# spokepov.net
KiCad netlist of a schematic drawn in EAGLE
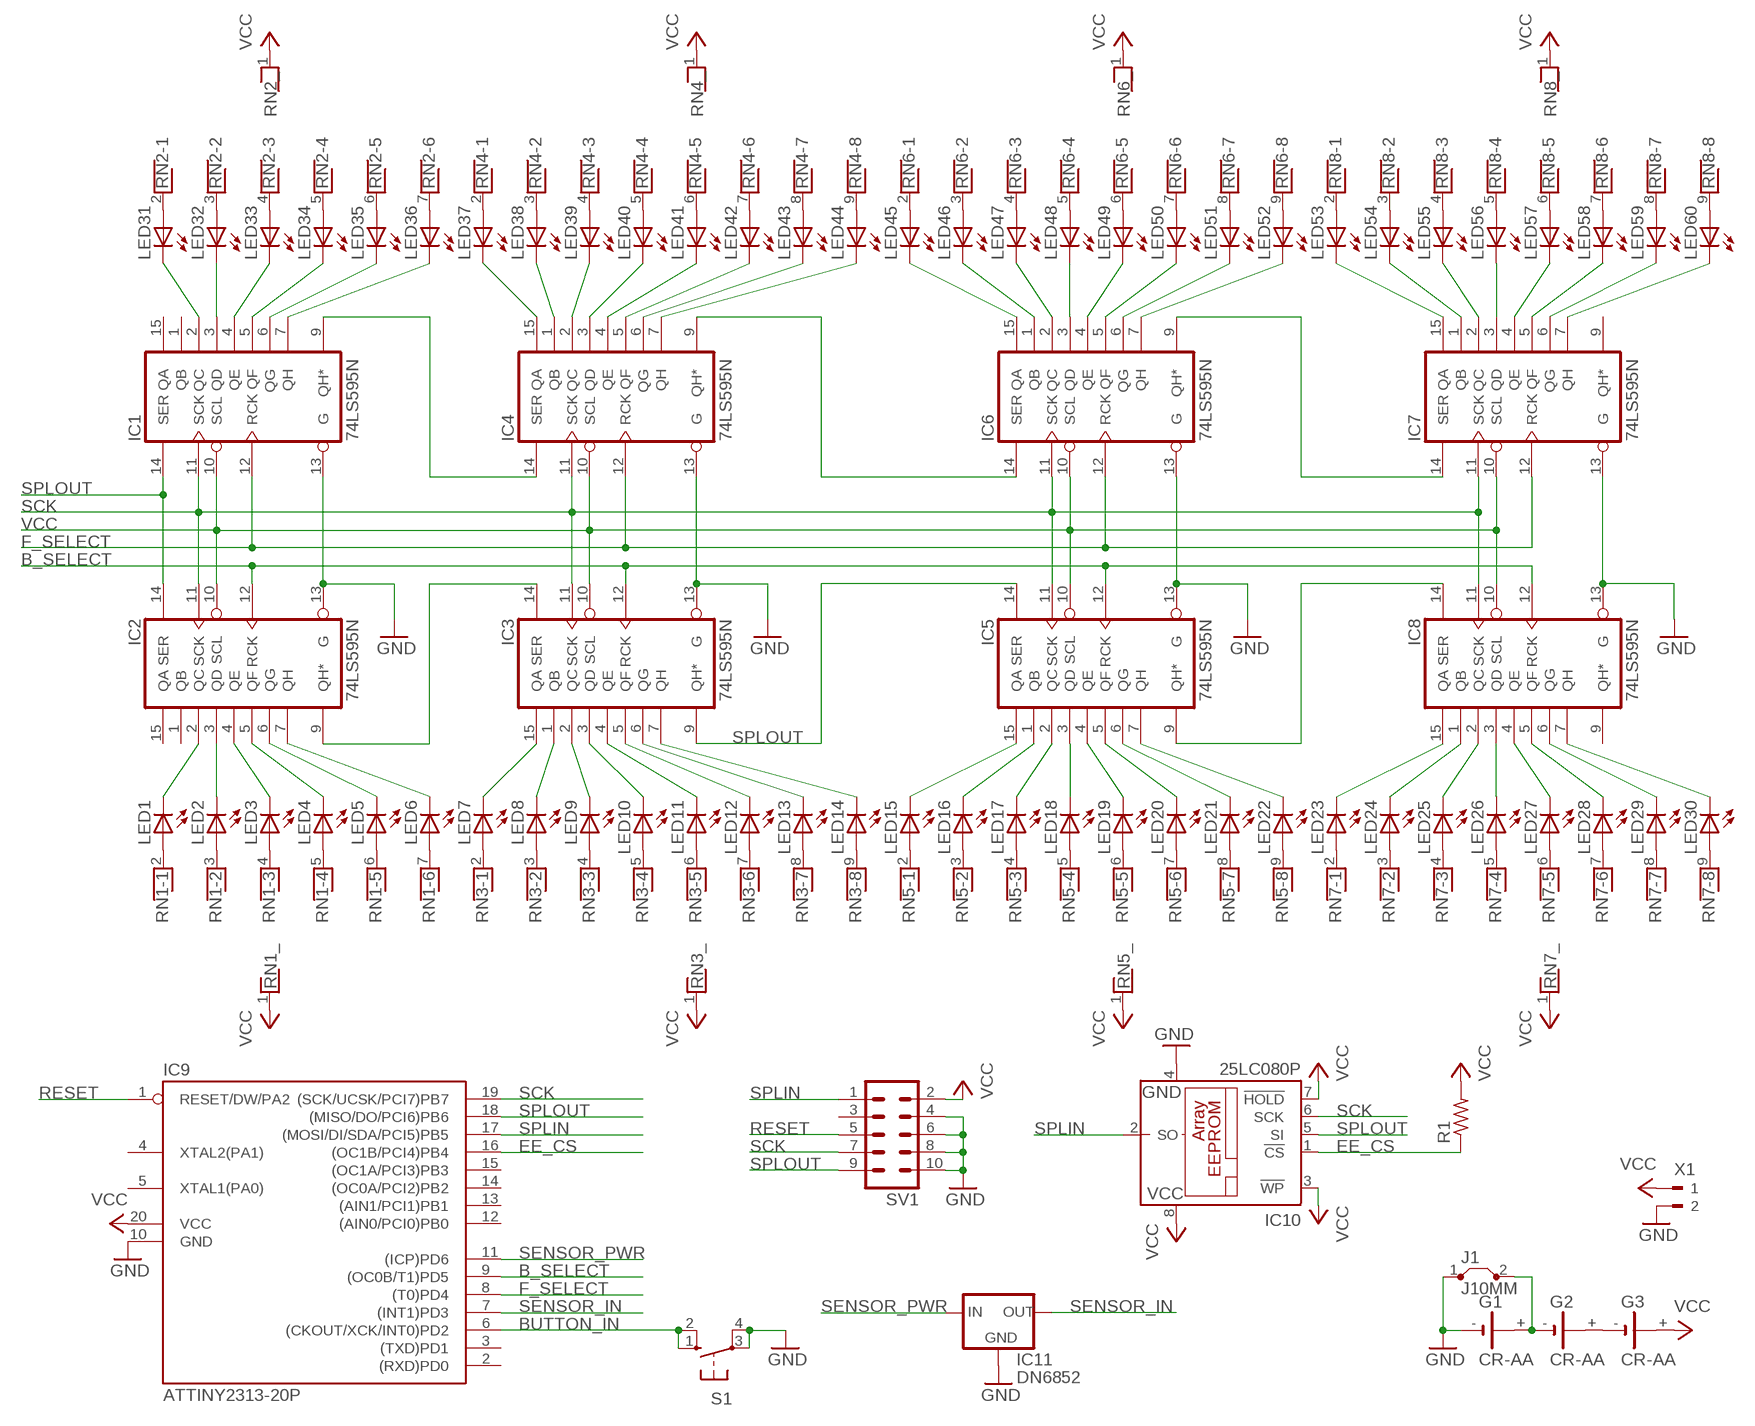
[diagram p0: schematic, sheet 1]

(export (version "E")
  (design (tool "Eeschema 10.0.6"))
  (components
    (comp (ref "G1")
      (value "CR-AA")
      (footprint "eagle-import:CRAA")
      (libsource (lib "eagle-import") (part "CR-AA"))
    )
    (comp (ref "G2")
      (value "CR-AA")
      (footprint "eagle-import:CRAA")
      (libsource (lib "eagle-import") (part "CR-AA"))
    )
    (comp (ref "G3")
      (value "CR-AA")
      (footprint "eagle-import:CRAA")
      (libsource (lib "eagle-import") (part "CR-AA"))
    )
    (comp (ref "IC1")
      (value "74LS595N")
      (footprint "eagle-import:DIL16")
      (libsource (lib "eagle-import") (part "74595NLS"))
    )
    (comp (ref "IC2")
      (value "74LS595N")
      (footprint "eagle-import:DIL16")
      (libsource (lib "eagle-import") (part "74595NLS"))
    )
    (comp (ref "IC3")
      (value "74LS595N")
      (footprint "eagle-import:DIL16")
      (libsource (lib "eagle-import") (part "74595NLS"))
    )
    (comp (ref "IC4")
      (value "74LS595N")
      (footprint "eagle-import:DIL16")
      (libsource (lib "eagle-import") (part "74595NLS"))
    )
    (comp (ref "IC5")
      (value "74LS595N")
      (footprint "eagle-import:DIL16")
      (libsource (lib "eagle-import") (part "74595NLS"))
    )
    (comp (ref "IC6")
      (value "74LS595N")
      (footprint "eagle-import:DIL16")
      (libsource (lib "eagle-import") (part "74595NLS"))
    )
    (comp (ref "IC7")
      (value "74LS595N")
      (footprint "eagle-import:DIL16")
      (libsource (lib "eagle-import") (part "74595NLS"))
    )
    (comp (ref "IC8")
      (value "74LS595N")
      (footprint "eagle-import:DIL16")
      (libsource (lib "eagle-import") (part "74595NLS"))
    )
    (comp (ref "IC9")
      (value "ATTINY2313-20P")
      (footprint "eagle-import:DIL20")
      (libsource (lib "eagle-import") (part "ATTINY2313P-20"))
    )
    (comp (ref "IC10")
      (value "25LC080P")
      (footprint "eagle-import:DIL8")
      (fields (field (name "MF") "MICROCHIP") (field (name "MPN") "25LC080/P"))
      (libsource (lib "eagle-import") (part "25PLC080"))
    )
    (comp (ref "IC11")
      (value "DN6852")
      (footprint "eagle-import:78MXXS")
      (libsource (lib "eagle-import") (part "78MXXS"))
    )
    (comp (ref "J1")
      (value "J10MM")
      (footprint "eagle-import:10")
      (libsource (lib "eagle-import") (part "J10MM"))
    )
    (comp (ref "LED1")
      (value "LED5MM")
      (footprint "eagle-import:LED5MM")
      (libsource (lib "eagle-import") (part "LED5MM"))
    )
    (comp (ref "LED2")
      (value "LED5MM")
      (footprint "eagle-import:LED5MM")
      (libsource (lib "eagle-import") (part "LED5MM"))
    )
    (comp (ref "LED3")
      (value "LED5MM")
      (footprint "eagle-import:LED5MM")
      (libsource (lib "eagle-import") (part "LED5MM"))
    )
    (comp (ref "LED4")
      (value "LED5MM")
      (footprint "eagle-import:LED5MM")
      (libsource (lib "eagle-import") (part "LED5MM"))
    )
    (comp (ref "LED5")
      (value "LED5MM")
      (footprint "eagle-import:LED5MM")
      (libsource (lib "eagle-import") (part "LED5MM"))
    )
    (comp (ref "LED6")
      (value "LED5MM")
      (footprint "eagle-import:LED5MM")
      (libsource (lib "eagle-import") (part "LED5MM"))
    )
    (comp (ref "LED7")
      (value "LED5MM")
      (footprint "eagle-import:LED5MM")
      (libsource (lib "eagle-import") (part "LED5MM"))
    )
    (comp (ref "LED8")
      (value "LED5MM")
      (footprint "eagle-import:LED5MM")
      (libsource (lib "eagle-import") (part "LED5MM"))
    )
    (comp (ref "LED9")
      (value "LED5MM")
      (footprint "eagle-import:LED5MM")
      (libsource (lib "eagle-import") (part "LED5MM"))
    )
    (comp (ref "LED10")
      (value "LED5MM")
      (footprint "eagle-import:LED5MM")
      (libsource (lib "eagle-import") (part "LED5MM"))
    )
    (comp (ref "LED11")
      (value "LED5MM")
      (footprint "eagle-import:LED5MM")
      (libsource (lib "eagle-import") (part "LED5MM"))
    )
    (comp (ref "LED12")
      (value "LED5MM")
      (footprint "eagle-import:LED5MM")
      (libsource (lib "eagle-import") (part "LED5MM"))
    )
    (comp (ref "LED13")
      (value "LED5MM")
      (footprint "eagle-import:LED5MM")
      (libsource (lib "eagle-import") (part "LED5MM"))
    )
    (comp (ref "LED14")
      (value "LED5MM")
      (footprint "eagle-import:LED5MM")
      (libsource (lib "eagle-import") (part "LED5MM"))
    )
    (comp (ref "LED15")
      (value "LED5MM")
      (footprint "eagle-import:LED5MM")
      (libsource (lib "eagle-import") (part "LED5MM"))
    )
    (comp (ref "LED16")
      (value "LED5MM")
      (footprint "eagle-import:LED5MM")
      (libsource (lib "eagle-import") (part "LED5MM"))
    )
    (comp (ref "LED17")
      (value "LED5MM")
      (footprint "eagle-import:LED5MM")
      (libsource (lib "eagle-import") (part "LED5MM"))
    )
    (comp (ref "LED18")
      (value "LED5MM")
      (footprint "eagle-import:LED5MM")
      (libsource (lib "eagle-import") (part "LED5MM"))
    )
    (comp (ref "LED19")
      (value "LED5MM")
      (footprint "eagle-import:LED5MM")
      (libsource (lib "eagle-import") (part "LED5MM"))
    )
    (comp (ref "LED20")
      (value "LED5MM")
      (footprint "eagle-import:LED5MM")
      (libsource (lib "eagle-import") (part "LED5MM"))
    )
    (comp (ref "LED21")
      (value "LED5MM")
      (footprint "eagle-import:LED5MM")
      (libsource (lib "eagle-import") (part "LED5MM"))
    )
    (comp (ref "LED22")
      (value "LED5MM")
      (footprint "eagle-import:LED5MM")
      (libsource (lib "eagle-import") (part "LED5MM"))
    )
    (comp (ref "LED23")
      (value "LED5MM")
      (footprint "eagle-import:LED5MM")
      (libsource (lib "eagle-import") (part "LED5MM"))
    )
    (comp (ref "LED24")
      (value "LED5MM")
      (footprint "eagle-import:LED5MM")
      (libsource (lib "eagle-import") (part "LED5MM"))
    )
    (comp (ref "LED25")
      (value "LED5MM")
      (footprint "eagle-import:LED5MM")
      (libsource (lib "eagle-import") (part "LED5MM"))
    )
    (comp (ref "LED26")
      (value "LED5MM")
      (footprint "eagle-import:LED5MM")
      (libsource (lib "eagle-import") (part "LED5MM"))
    )
    (comp (ref "LED27")
      (value "LED5MM")
      (footprint "eagle-import:LED5MM")
      (libsource (lib "eagle-import") (part "LED5MM"))
    )
    (comp (ref "LED28")
      (value "LED5MM")
      (footprint "eagle-import:LED5MM")
      (libsource (lib "eagle-import") (part "LED5MM"))
    )
    (comp (ref "LED29")
      (value "LED5MM")
      (footprint "eagle-import:LED5MM")
      (libsource (lib "eagle-import") (part "LED5MM"))
    )
    (comp (ref "LED30")
      (value "LED5MM")
      (footprint "eagle-import:LED5MM")
      (libsource (lib "eagle-import") (part "LED5MM"))
    )
    (comp (ref "LED31")
      (value "LED5MM")
      (footprint "eagle-import:LED5MM")
      (libsource (lib "eagle-import") (part "LED5MM"))
    )
    (comp (ref "LED32")
      (value "LED5MM")
      (footprint "eagle-import:LED5MM")
      (libsource (lib "eagle-import") (part "LED5MM"))
    )
    (comp (ref "LED33")
      (value "LED5MM")
      (footprint "eagle-import:LED5MM")
      (libsource (lib "eagle-import") (part "LED5MM"))
    )
    (comp (ref "LED34")
      (value "LED5MM")
      (footprint "eagle-import:LED5MM")
      (libsource (lib "eagle-import") (part "LED5MM"))
    )
    (comp (ref "LED35")
      (value "LED5MM")
      (footprint "eagle-import:LED5MM")
      (libsource (lib "eagle-import") (part "LED5MM"))
    )
    (comp (ref "LED36")
      (value "LED5MM")
      (footprint "eagle-import:LED5MM")
      (libsource (lib "eagle-import") (part "LED5MM"))
    )
    (comp (ref "LED37")
      (value "LED5MM")
      (footprint "eagle-import:LED5MM")
      (libsource (lib "eagle-import") (part "LED5MM"))
    )
    (comp (ref "LED38")
      (value "LED5MM")
      (footprint "eagle-import:LED5MM")
      (libsource (lib "eagle-import") (part "LED5MM"))
    )
    (comp (ref "LED39")
      (value "LED5MM")
      (footprint "eagle-import:LED5MM")
      (libsource (lib "eagle-import") (part "LED5MM"))
    )
    (comp (ref "LED40")
      (value "LED5MM")
      (footprint "eagle-import:LED5MM")
      (libsource (lib "eagle-import") (part "LED5MM"))
    )
    (comp (ref "LED41")
      (value "LED5MM")
      (footprint "eagle-import:LED5MM")
      (libsource (lib "eagle-import") (part "LED5MM"))
    )
    (comp (ref "LED42")
      (value "LED5MM")
      (footprint "eagle-import:LED5MM")
      (libsource (lib "eagle-import") (part "LED5MM"))
    )
    (comp (ref "LED43")
      (value "LED5MM")
      (footprint "eagle-import:LED5MM")
      (libsource (lib "eagle-import") (part "LED5MM"))
    )
    (comp (ref "LED44")
      (value "LED5MM")
      (footprint "eagle-import:LED5MM")
      (libsource (lib "eagle-import") (part "LED5MM"))
    )
    (comp (ref "LED45")
      (value "LED5MM")
      (footprint "eagle-import:LED5MM")
      (libsource (lib "eagle-import") (part "LED5MM"))
    )
    (comp (ref "LED46")
      (value "LED5MM")
      (footprint "eagle-import:LED5MM")
      (libsource (lib "eagle-import") (part "LED5MM"))
    )
    (comp (ref "LED47")
      (value "LED5MM")
      (footprint "eagle-import:LED5MM")
      (libsource (lib "eagle-import") (part "LED5MM"))
    )
    (comp (ref "LED48")
      (value "LED5MM")
      (footprint "eagle-import:LED5MM")
      (libsource (lib "eagle-import") (part "LED5MM"))
    )
    (comp (ref "LED49")
      (value "LED5MM")
      (footprint "eagle-import:LED5MM")
      (libsource (lib "eagle-import") (part "LED5MM"))
    )
    (comp (ref "LED50")
      (value "LED5MM")
      (footprint "eagle-import:LED5MM")
      (libsource (lib "eagle-import") (part "LED5MM"))
    )
    (comp (ref "LED51")
      (value "LED5MM")
      (footprint "eagle-import:LED5MM")
      (libsource (lib "eagle-import") (part "LED5MM"))
    )
    (comp (ref "LED52")
      (value "LED5MM")
      (footprint "eagle-import:LED5MM")
      (libsource (lib "eagle-import") (part "LED5MM"))
    )
    (comp (ref "LED53")
      (value "LED5MM")
      (footprint "eagle-import:LED5MM")
      (libsource (lib "eagle-import") (part "LED5MM"))
    )
    (comp (ref "LED54")
      (value "LED5MM")
      (footprint "eagle-import:LED5MM")
      (libsource (lib "eagle-import") (part "LED5MM"))
    )
    (comp (ref "LED55")
      (value "LED5MM")
      (footprint "eagle-import:LED5MM")
      (libsource (lib "eagle-import") (part "LED5MM"))
    )
    (comp (ref "LED56")
      (value "LED5MM")
      (footprint "eagle-import:LED5MM")
      (libsource (lib "eagle-import") (part "LED5MM"))
    )
    (comp (ref "LED57")
      (value "LED5MM")
      (footprint "eagle-import:LED5MM")
      (libsource (lib "eagle-import") (part "LED5MM"))
    )
    (comp (ref "LED58")
      (value "LED5MM")
      (footprint "eagle-import:LED5MM")
      (libsource (lib "eagle-import") (part "LED5MM"))
    )
    (comp (ref "LED59")
      (value "LED5MM")
      (footprint "eagle-import:LED5MM")
      (libsource (lib "eagle-import") (part "LED5MM"))
    )
    (comp (ref "LED60")
      (value "LED5MM")
      (footprint "eagle-import:LED5MM")
      (libsource (lib "eagle-import") (part "LED5MM"))
    )
    (comp (ref "R1")
      (value "R-US_0207/10")
      (footprint "eagle-import:0207_10")
      (libsource (lib "eagle-import") (part "R-US_0207/10"))
    )
    (comp (ref "RN1")
      (value "RNX8")
      (footprint "eagle-import:RN-9")
      (libsource (lib "eagle-import") (part "RNX8"))
    )
    (comp (ref "RN2")
      (value "RNX8")
      (footprint "eagle-import:RN-9")
      (libsource (lib "eagle-import") (part "RNX8"))
    )
    (comp (ref "RN3")
      (value "RNX8")
      (footprint "eagle-import:RN-9")
      (libsource (lib "eagle-import") (part "RNX8"))
    )
    (comp (ref "RN4")
      (value "RNX8")
      (footprint "eagle-import:RN-9")
      (libsource (lib "eagle-import") (part "RNX8"))
    )
    (comp (ref "RN5")
      (value "RNX8")
      (footprint "eagle-import:RN-9")
      (libsource (lib "eagle-import") (part "RNX8"))
    )
    (comp (ref "RN6")
      (value "RNX8")
      (footprint "eagle-import:RN-9")
      (libsource (lib "eagle-import") (part "RNX8"))
    )
    (comp (ref "RN7")
      (value "RNX8")
      (footprint "eagle-import:RN-9")
      (libsource (lib "eagle-import") (part "RNX8"))
    )
    (comp (ref "RN8")
      (value "RNX8")
      (footprint "eagle-import:RN-9")
      (libsource (lib "eagle-import") (part "RNX8"))
    )
    (comp (ref "S1")
      (value "10-XX")
      (footprint "eagle-import:B3F-10XX")
      (fields (field (name "MPN") "B3F-1000"))
      (libsource (lib "eagle-import") (part "10-XX"))
    )
    (comp (ref "SV1")
      (value "ML10")
      (footprint "eagle-import:ML10")
      (libsource (lib "eagle-import") (part "ML10"))
    )
    (comp (ref "X1")
      (value "90-2")
      (footprint "eagle-import:90-2")
      (libsource (lib "eagle-import") (part "90-2"))
    )
  )
  (nets
    (net (code "1") (name "/BUTTON_IN") (class "Default")
      (node (ref "IC9") (pin "6") (pinfunction "(CKOUT/XCK/INT0)PD2_6") (pintype "bidirectional"))
      (node (ref "S1") (pin "1") (pinfunction "S_1") (pintype "passive"))
      (node (ref "S1") (pin "2") (pinfunction "S1_2") (pintype "passive"))
    )
    (net (code "2") (name "/B_SELECT") (class "Default")
      (node (ref "IC2") (pin "12") (pinfunction "RCK_12") (pintype "input"))
      (node (ref "IC3") (pin "12") (pinfunction "RCK_12") (pintype "input"))
      (node (ref "IC5") (pin "12") (pinfunction "RCK_12") (pintype "input"))
      (node (ref "IC8") (pin "12") (pinfunction "RCK_12") (pintype "input"))
      (node (ref "IC9") (pin "9") (pinfunction "(OC0B/T1)PD5_9") (pintype "bidirectional"))
    )
    (net (code "3") (name "/EE_CS") (class "Default")
      (node (ref "IC10") (pin "1") (pinfunction "~{CS}_1") (pintype "input"))
      (node (ref "IC9") (pin "16") (pinfunction "(OC1B/PCI4)PB4_16") (pintype "bidirectional"))
      (node (ref "R1") (pin "1") (pinfunction "1_1") (pintype "passive"))
    )
    (net (code "4") (name "/F_SELECT") (class "Default")
      (node (ref "IC1") (pin "12") (pinfunction "RCK_12") (pintype "input"))
      (node (ref "IC4") (pin "12") (pinfunction "RCK_12") (pintype "input"))
      (node (ref "IC6") (pin "12") (pinfunction "RCK_12") (pintype "input"))
      (node (ref "IC7") (pin "12") (pinfunction "RCK_12") (pintype "input"))
      (node (ref "IC9") (pin "8") (pinfunction "(T0)PD4_8") (pintype "bidirectional"))
    )
    (net (code "5") (name "/RESET") (class "Default")
      (node (ref "IC9") (pin "1") (pinfunction "RESET/DW/PA2_1") (pintype "bidirectional"))
      (node (ref "SV1") (pin "5") (pinfunction "5_5") (pintype "passive"))
    )
    (net (code "6") (name "/SCK") (class "Default")
      (node (ref "IC1") (pin "11") (pinfunction "SCK_11") (pintype "input"))
      (node (ref "IC10") (pin "6") (pinfunction "SCK_6") (pintype "input"))
      (node (ref "IC2") (pin "11") (pinfunction "SCK_11") (pintype "input"))
      (node (ref "IC3") (pin "11") (pinfunction "SCK_11") (pintype "input"))
      (node (ref "IC4") (pin "11") (pinfunction "SCK_11") (pintype "input"))
      (node (ref "IC5") (pin "11") (pinfunction "SCK_11") (pintype "input"))
      (node (ref "IC6") (pin "11") (pinfunction "SCK_11") (pintype "input"))
      (node (ref "IC7") (pin "11") (pinfunction "SCK_11") (pintype "input"))
      (node (ref "IC8") (pin "11") (pinfunction "SCK_11") (pintype "input"))
      (node (ref "IC9") (pin "19") (pinfunction "(SCK/UCSK/PCI7)PB7_19") (pintype "bidirectional"))
      (node (ref "SV1") (pin "7") (pinfunction "7_7") (pintype "passive"))
    )
    (net (code "7") (name "/SENSOR_IN") (class "Default")
      (node (ref "IC11") (pin "OUT") (pinfunction "OUT_OUT") (pintype "passive"))
      (node (ref "IC9") (pin "7") (pinfunction "(INT1)PD3_7") (pintype "bidirectional"))
    )
    (net (code "8") (name "/SENSOR_PWR") (class "Default")
      (node (ref "IC11") (pin "IN") (pinfunction "IN_IN") (pintype "input"))
      (node (ref "IC9") (pin "11") (pinfunction "(ICP)PD6_11") (pintype "bidirectional"))
    )
    (net (code "9") (name "/SPLIN") (class "Default")
      (node (ref "IC10") (pin "2") (pinfunction "SO_2") (pintype "bidirectional"))
      (node (ref "IC9") (pin "17") (pinfunction "(MOSI/DI/SDA/PCI5)PB5_17") (pintype "bidirectional"))
      (node (ref "SV1") (pin "1") (pinfunction "1_1") (pintype "passive"))
    )
    (net (code "10") (name "/SPLOUT") (class "Default")
      (node (ref "IC1") (pin "14") (pinfunction "SER_14") (pintype "input"))
      (node (ref "IC10") (pin "5") (pinfunction "SI_5") (pintype "input"))
      (node (ref "IC2") (pin "14") (pinfunction "SER_14") (pintype "input"))
      (node (ref "IC3") (pin "9") (pinfunction "QH*_9") (pintype "tri_state"))
      (node (ref "IC5") (pin "14") (pinfunction "SER_14") (pintype "input"))
      (node (ref "IC9") (pin "18") (pinfunction "(MISO/DO/PCI6)PB6_18") (pintype "bidirectional"))
      (node (ref "SV1") (pin "9") (pinfunction "9_9") (pintype "passive"))
    )
    (net (code "11") (name "GND") (class "Default")
      (node (ref "G1") (pin "-") (pinfunction "-_-") (pintype "passive"))
      (node (ref "IC1") (pin "13") (pinfunction "G_13") (pintype "input"))
      (node (ref "IC10") (pin "4") (pinfunction "GND_4") (pintype "power_in"))
      (node (ref "IC11") (pin "GND") (pinfunction "GND_GND") (pintype "input"))
      (node (ref "IC2") (pin "13") (pinfunction "G_13") (pintype "input"))
      (node (ref "IC3") (pin "13") (pinfunction "G_13") (pintype "input"))
      (node (ref "IC4") (pin "13") (pinfunction "G_13") (pintype "input"))
      (node (ref "IC5") (pin "13") (pinfunction "G_13") (pintype "input"))
      (node (ref "IC6") (pin "13") (pinfunction "G_13") (pintype "input"))
      (node (ref "IC7") (pin "13") (pinfunction "G_13") (pintype "input"))
      (node (ref "IC8") (pin "13") (pinfunction "G_13") (pintype "input"))
      (node (ref "IC9") (pin "10") (pinfunction "GND_10") (pintype "power_in"))
      (node (ref "J1") (pin "1") (pinfunction "1_1") (pintype "passive"))
      (node (ref "S1") (pin "3") (pinfunction "P_3") (pintype "passive"))
      (node (ref "S1") (pin "4") (pinfunction "P1_4") (pintype "passive"))
      (node (ref "SV1") (pin "10") (pinfunction "10_10") (pintype "passive"))
      (node (ref "SV1") (pin "4") (pinfunction "4_4") (pintype "passive"))
      (node (ref "SV1") (pin "6") (pinfunction "6_6") (pintype "passive"))
      (node (ref "SV1") (pin "8") (pinfunction "8_8") (pintype "passive"))
      (node (ref "X1") (pin "2") (pinfunction "2_2") (pintype "passive"))
    )
    (net (code "12") (name "Net-(G1-Pad+)") (class "Default")
      (node (ref "G1") (pin "+") (pinfunction "+_+") (pintype "passive"))
      (node (ref "G2") (pin "-") (pinfunction "-_-") (pintype "passive"))
      (node (ref "J1") (pin "2") (pinfunction "2_2") (pintype "passive"))
    )
    (net (code "13") (name "Net-(G2-Pad+)") (class "Default")
      (node (ref "G2") (pin "+") (pinfunction "+_+") (pintype "passive"))
      (node (ref "G3") (pin "-") (pinfunction "-_-") (pintype "passive"))
    )
    (net (code "14") (name "Net-(IC1A-QC)") (class "Default")
      (node (ref "IC1") (pin "2") (pinfunction "QC_2") (pintype "tri_state"))
      (node (ref "LED31") (pin "K") (pinfunction "C_K") (pintype "passive"))
    )
    (net (code "15") (name "Net-(IC1A-QD)") (class "Default")
      (node (ref "IC1") (pin "3") (pinfunction "QD_3") (pintype "tri_state"))
      (node (ref "LED32") (pin "K") (pinfunction "C_K") (pintype "passive"))
    )
    (net (code "16") (name "Net-(IC1A-QE)") (class "Default")
      (node (ref "IC1") (pin "4") (pinfunction "QE_4") (pintype "tri_state"))
      (node (ref "LED33") (pin "K") (pinfunction "C_K") (pintype "passive"))
    )
    (net (code "17") (name "Net-(IC1A-QF)") (class "Default")
      (node (ref "IC1") (pin "5") (pinfunction "QF_5") (pintype "tri_state"))
      (node (ref "LED34") (pin "K") (pinfunction "C_K") (pintype "passive"))
    )
    (net (code "18") (name "Net-(IC1A-QG)") (class "Default")
      (node (ref "IC1") (pin "6") (pinfunction "QG_6") (pintype "tri_state"))
      (node (ref "LED35") (pin "K") (pinfunction "C_K") (pintype "passive"))
    )
    (net (code "19") (name "Net-(IC1A-QH)") (class "Default")
      (node (ref "IC1") (pin "7") (pinfunction "QH_7") (pintype "tri_state"))
      (node (ref "LED36") (pin "K") (pinfunction "C_K") (pintype "passive"))
    )
    (net (code "20") (name "Net-(IC1A-QH*)") (class "Default")
      (node (ref "IC1") (pin "9") (pinfunction "QH*_9") (pintype "tri_state"))
      (node (ref "IC4") (pin "14") (pinfunction "SER_14") (pintype "input"))
    )
    (net (code "21") (name "Net-(IC2A-QC)") (class "Default")
      (node (ref "IC2") (pin "2") (pinfunction "QC_2") (pintype "tri_state"))
      (node (ref "LED1") (pin "K") (pinfunction "C_K") (pintype "passive"))
    )
    (net (code "22") (name "Net-(IC2A-QD)") (class "Default")
      (node (ref "IC2") (pin "3") (pinfunction "QD_3") (pintype "tri_state"))
      (node (ref "LED2") (pin "K") (pinfunction "C_K") (pintype "passive"))
    )
    (net (code "23") (name "Net-(IC2A-QE)") (class "Default")
      (node (ref "IC2") (pin "4") (pinfunction "QE_4") (pintype "tri_state"))
      (node (ref "LED3") (pin "K") (pinfunction "C_K") (pintype "passive"))
    )
    (net (code "24") (name "Net-(IC2A-QF)") (class "Default")
      (node (ref "IC2") (pin "5") (pinfunction "QF_5") (pintype "tri_state"))
      (node (ref "LED4") (pin "K") (pinfunction "C_K") (pintype "passive"))
    )
    (net (code "25") (name "Net-(IC2A-QG)") (class "Default")
      (node (ref "IC2") (pin "6") (pinfunction "QG_6") (pintype "tri_state"))
      (node (ref "LED5") (pin "K") (pinfunction "C_K") (pintype "passive"))
    )
    (net (code "26") (name "Net-(IC2A-QH)") (class "Default")
      (node (ref "IC2") (pin "7") (pinfunction "QH_7") (pintype "tri_state"))
      (node (ref "LED6") (pin "K") (pinfunction "C_K") (pintype "passive"))
    )
    (net (code "27") (name "Net-(IC2A-QH*)") (class "Default")
      (node (ref "IC2") (pin "9") (pinfunction "QH*_9") (pintype "tri_state"))
      (node (ref "IC3") (pin "14") (pinfunction "SER_14") (pintype "input"))
    )
    (net (code "28") (name "Net-(IC3A-QA)") (class "Default")
      (node (ref "IC3") (pin "15") (pinfunction "QA_15") (pintype "tri_state"))
      (node (ref "LED7") (pin "K") (pinfunction "C_K") (pintype "passive"))
    )
    (net (code "29") (name "Net-(IC3A-QB)") (class "Default")
      (node (ref "IC3") (pin "1") (pinfunction "QB_1") (pintype "tri_state"))
      (node (ref "LED8") (pin "K") (pinfunction "C_K") (pintype "passive"))
    )
    (net (code "30") (name "Net-(IC3A-QC)") (class "Default")
      (node (ref "IC3") (pin "2") (pinfunction "QC_2") (pintype "tri_state"))
      (node (ref "LED9") (pin "K") (pinfunction "C_K") (pintype "passive"))
    )
    (net (code "31") (name "Net-(IC3A-QD)") (class "Default")
      (node (ref "IC3") (pin "3") (pinfunction "QD_3") (pintype "tri_state"))
      (node (ref "LED10") (pin "K") (pinfunction "C_K") (pintype "passive"))
    )
    (net (code "32") (name "Net-(IC3A-QE)") (class "Default")
      (node (ref "IC3") (pin "4") (pinfunction "QE_4") (pintype "tri_state"))
      (node (ref "LED11") (pin "K") (pinfunction "C_K") (pintype "passive"))
    )
    (net (code "33") (name "Net-(IC3A-QF)") (class "Default")
      (node (ref "IC3") (pin "5") (pinfunction "QF_5") (pintype "tri_state"))
      (node (ref "LED12") (pin "K") (pinfunction "C_K") (pintype "passive"))
    )
    (net (code "34") (name "Net-(IC3A-QG)") (class "Default")
      (node (ref "IC3") (pin "6") (pinfunction "QG_6") (pintype "tri_state"))
      (node (ref "LED13") (pin "K") (pinfunction "C_K") (pintype "passive"))
    )
    (net (code "35") (name "Net-(IC3A-QH)") (class "Default")
      (node (ref "IC3") (pin "7") (pinfunction "QH_7") (pintype "tri_state"))
      (node (ref "LED14") (pin "K") (pinfunction "C_K") (pintype "passive"))
    )
    (net (code "36") (name "Net-(IC4A-QA)") (class "Default")
      (node (ref "IC4") (pin "15") (pinfunction "QA_15") (pintype "tri_state"))
      (node (ref "LED37") (pin "K") (pinfunction "C_K") (pintype "passive"))
    )
    (net (code "37") (name "Net-(IC4A-QB)") (class "Default")
      (node (ref "IC4") (pin "1") (pinfunction "QB_1") (pintype "tri_state"))
      (node (ref "LED38") (pin "K") (pinfunction "C_K") (pintype "passive"))
    )
    (net (code "38") (name "Net-(IC4A-QC)") (class "Default")
      (node (ref "IC4") (pin "2") (pinfunction "QC_2") (pintype "tri_state"))
      (node (ref "LED39") (pin "K") (pinfunction "C_K") (pintype "passive"))
    )
    (net (code "39") (name "Net-(IC4A-QD)") (class "Default")
      (node (ref "IC4") (pin "3") (pinfunction "QD_3") (pintype "tri_state"))
      (node (ref "LED40") (pin "K") (pinfunction "C_K") (pintype "passive"))
    )
    (net (code "40") (name "Net-(IC4A-QE)") (class "Default")
      (node (ref "IC4") (pin "4") (pinfunction "QE_4") (pintype "tri_state"))
      (node (ref "LED41") (pin "K") (pinfunction "C_K") (pintype "passive"))
    )
    (net (code "41") (name "Net-(IC4A-QF)") (class "Default")
      (node (ref "IC4") (pin "5") (pinfunction "QF_5") (pintype "tri_state"))
      (node (ref "LED42") (pin "K") (pinfunction "C_K") (pintype "passive"))
    )
    (net (code "42") (name "Net-(IC4A-QG)") (class "Default")
      (node (ref "IC4") (pin "6") (pinfunction "QG_6") (pintype "tri_state"))
      (node (ref "LED43") (pin "K") (pinfunction "C_K") (pintype "passive"))
    )
    (net (code "43") (name "Net-(IC4A-QH)") (class "Default")
      (node (ref "IC4") (pin "7") (pinfunction "QH_7") (pintype "tri_state"))
      (node (ref "LED44") (pin "K") (pinfunction "C_K") (pintype "passive"))
    )
    (net (code "44") (name "Net-(IC4A-QH*)") (class "Default")
      (node (ref "IC4") (pin "9") (pinfunction "QH*_9") (pintype "tri_state"))
      (node (ref "IC6") (pin "14") (pinfunction "SER_14") (pintype "input"))
    )
    (net (code "45") (name "Net-(IC5A-QA)") (class "Default")
      (node (ref "IC5") (pin "15") (pinfunction "QA_15") (pintype "tri_state"))
      (node (ref "LED15") (pin "K") (pinfunction "C_K") (pintype "passive"))
    )
    (net (code "46") (name "Net-(IC5A-QB)") (class "Default")
      (node (ref "IC5") (pin "1") (pinfunction "QB_1") (pintype "tri_state"))
      (node (ref "LED16") (pin "K") (pinfunction "C_K") (pintype "passive"))
    )
    (net (code "47") (name "Net-(IC5A-QC)") (class "Default")
      (node (ref "IC5") (pin "2") (pinfunction "QC_2") (pintype "tri_state"))
      (node (ref "LED17") (pin "K") (pinfunction "C_K") (pintype "passive"))
    )
    (net (code "48") (name "Net-(IC5A-QD)") (class "Default")
      (node (ref "IC5") (pin "3") (pinfunction "QD_3") (pintype "tri_state"))
      (node (ref "LED18") (pin "K") (pinfunction "C_K") (pintype "passive"))
    )
    (net (code "49") (name "Net-(IC5A-QE)") (class "Default")
      (node (ref "IC5") (pin "4") (pinfunction "QE_4") (pintype "tri_state"))
      (node (ref "LED19") (pin "K") (pinfunction "C_K") (pintype "passive"))
    )
    (net (code "50") (name "Net-(IC5A-QF)") (class "Default")
      (node (ref "IC5") (pin "5") (pinfunction "QF_5") (pintype "tri_state"))
      (node (ref "LED20") (pin "K") (pinfunction "C_K") (pintype "passive"))
    )
    (net (code "51") (name "Net-(IC5A-QG)") (class "Default")
      (node (ref "IC5") (pin "6") (pinfunction "QG_6") (pintype "tri_state"))
      (node (ref "LED21") (pin "K") (pinfunction "C_K") (pintype "passive"))
    )
    (net (code "52") (name "Net-(IC5A-QH)") (class "Default")
      (node (ref "IC5") (pin "7") (pinfunction "QH_7") (pintype "tri_state"))
      (node (ref "LED22") (pin "K") (pinfunction "C_K") (pintype "passive"))
    )
    (net (code "53") (name "Net-(IC5A-QH*)") (class "Default")
      (node (ref "IC5") (pin "9") (pinfunction "QH*_9") (pintype "tri_state"))
      (node (ref "IC8") (pin "14") (pinfunction "SER_14") (pintype "input"))
    )
    (net (code "54") (name "Net-(IC6A-QA)") (class "Default")
      (node (ref "IC6") (pin "15") (pinfunction "QA_15") (pintype "tri_state"))
      (node (ref "LED45") (pin "K") (pinfunction "C_K") (pintype "passive"))
    )
    (net (code "55") (name "Net-(IC6A-QB)") (class "Default")
      (node (ref "IC6") (pin "1") (pinfunction "QB_1") (pintype "tri_state"))
      (node (ref "LED46") (pin "K") (pinfunction "C_K") (pintype "passive"))
    )
    (net (code "56") (name "Net-(IC6A-QC)") (class "Default")
      (node (ref "IC6") (pin "2") (pinfunction "QC_2") (pintype "tri_state"))
      (node (ref "LED47") (pin "K") (pinfunction "C_K") (pintype "passive"))
    )
    (net (code "57") (name "Net-(IC6A-QD)") (class "Default")
      (node (ref "IC6") (pin "3") (pinfunction "QD_3") (pintype "tri_state"))
      (node (ref "LED48") (pin "K") (pinfunction "C_K") (pintype "passive"))
    )
    (net (code "58") (name "Net-(IC6A-QE)") (class "Default")
      (node (ref "IC6") (pin "4") (pinfunction "QE_4") (pintype "tri_state"))
      (node (ref "LED49") (pin "K") (pinfunction "C_K") (pintype "passive"))
    )
    (net (code "59") (name "Net-(IC6A-QF)") (class "Default")
      (node (ref "IC6") (pin "5") (pinfunction "QF_5") (pintype "tri_state"))
      (node (ref "LED50") (pin "K") (pinfunction "C_K") (pintype "passive"))
    )
    (net (code "60") (name "Net-(IC6A-QG)") (class "Default")
      (node (ref "IC6") (pin "6") (pinfunction "QG_6") (pintype "tri_state"))
      (node (ref "LED51") (pin "K") (pinfunction "C_K") (pintype "passive"))
    )
    (net (code "61") (name "Net-(IC6A-QH)") (class "Default")
      (node (ref "IC6") (pin "7") (pinfunction "QH_7") (pintype "tri_state"))
      (node (ref "LED52") (pin "K") (pinfunction "C_K") (pintype "passive"))
    )
    (net (code "62") (name "Net-(IC6A-QH*)") (class "Default")
      (node (ref "IC6") (pin "9") (pinfunction "QH*_9") (pintype "tri_state"))
      (node (ref "IC7") (pin "14") (pinfunction "SER_14") (pintype "input"))
    )
    (net (code "63") (name "Net-(IC7A-QA)") (class "Default")
      (node (ref "IC7") (pin "15") (pinfunction "QA_15") (pintype "tri_state"))
      (node (ref "LED53") (pin "K") (pinfunction "C_K") (pintype "passive"))
    )
    (net (code "64") (name "Net-(IC7A-QB)") (class "Default")
      (node (ref "IC7") (pin "1") (pinfunction "QB_1") (pintype "tri_state"))
      (node (ref "LED54") (pin "K") (pinfunction "C_K") (pintype "passive"))
    )
    (net (code "65") (name "Net-(IC7A-QC)") (class "Default")
      (node (ref "IC7") (pin "2") (pinfunction "QC_2") (pintype "tri_state"))
      (node (ref "LED55") (pin "K") (pinfunction "C_K") (pintype "passive"))
    )
    (net (code "66") (name "Net-(IC7A-QD)") (class "Default")
      (node (ref "IC7") (pin "3") (pinfunction "QD_3") (pintype "tri_state"))
      (node (ref "LED56") (pin "K") (pinfunction "C_K") (pintype "passive"))
    )
    (net (code "67") (name "Net-(IC7A-QE)") (class "Default")
      (node (ref "IC7") (pin "4") (pinfunction "QE_4") (pintype "tri_state"))
      (node (ref "LED57") (pin "K") (pinfunction "C_K") (pintype "passive"))
    )
    (net (code "68") (name "Net-(IC7A-QF)") (class "Default")
      (node (ref "IC7") (pin "5") (pinfunction "QF_5") (pintype "tri_state"))
      (node (ref "LED58") (pin "K") (pinfunction "C_K") (pintype "passive"))
    )
    (net (code "69") (name "Net-(IC7A-QG)") (class "Default")
      (node (ref "IC7") (pin "6") (pinfunction "QG_6") (pintype "tri_state"))
      (node (ref "LED59") (pin "K") (pinfunction "C_K") (pintype "passive"))
    )
    (net (code "70") (name "Net-(IC7A-QH)") (class "Default")
      (node (ref "IC7") (pin "7") (pinfunction "QH_7") (pintype "tri_state"))
      (node (ref "LED60") (pin "K") (pinfunction "C_K") (pintype "passive"))
    )
    (net (code "71") (name "Net-(IC8A-QA)") (class "Default")
      (node (ref "IC8") (pin "15") (pinfunction "QA_15") (pintype "tri_state"))
      (node (ref "LED23") (pin "K") (pinfunction "C_K") (pintype "passive"))
    )
    (net (code "72") (name "Net-(IC8A-QB)") (class "Default")
      (node (ref "IC8") (pin "1") (pinfunction "QB_1") (pintype "tri_state"))
      (node (ref "LED24") (pin "K") (pinfunction "C_K") (pintype "passive"))
    )
    (net (code "73") (name "Net-(IC8A-QC)") (class "Default")
      (node (ref "IC8") (pin "2") (pinfunction "QC_2") (pintype "tri_state"))
      (node (ref "LED25") (pin "K") (pinfunction "C_K") (pintype "passive"))
    )
    (net (code "74") (name "Net-(IC8A-QD)") (class "Default")
      (node (ref "IC8") (pin "3") (pinfunction "QD_3") (pintype "tri_state"))
      (node (ref "LED26") (pin "K") (pinfunction "C_K") (pintype "passive"))
    )
    (net (code "75") (name "Net-(IC8A-QE)") (class "Default")
      (node (ref "IC8") (pin "4") (pinfunction "QE_4") (pintype "tri_state"))
      (node (ref "LED27") (pin "K") (pinfunction "C_K") (pintype "passive"))
    )
    (net (code "76") (name "Net-(IC8A-QF)") (class "Default")
      (node (ref "IC8") (pin "5") (pinfunction "QF_5") (pintype "tri_state"))
      (node (ref "LED28") (pin "K") (pinfunction "C_K") (pintype "passive"))
    )
    (net (code "77") (name "Net-(IC8A-QG)") (class "Default")
      (node (ref "IC8") (pin "6") (pinfunction "QG_6") (pintype "tri_state"))
      (node (ref "LED29") (pin "K") (pinfunction "C_K") (pintype "passive"))
    )
    (net (code "78") (name "Net-(IC8A-QH)") (class "Default")
      (node (ref "IC8") (pin "7") (pinfunction "QH_7") (pintype "tri_state"))
      (node (ref "LED30") (pin "K") (pinfunction "C_K") (pintype "passive"))
    )
    (net (code "79") (name "Net-(RN1A-1)") (class "Default")
      (node (ref "LED1") (pin "A") (pinfunction "A_A") (pintype "passive"))
      (node (ref "RN1") (pin "2") (pinfunction "1_2") (pintype "passive"))
    )
    (net (code "80") (name "Net-(RN1B-1)") (class "Default")
      (node (ref "LED2") (pin "A") (pinfunction "A_A") (pintype "passive"))
      (node (ref "RN1") (pin "3") (pinfunction "1_3") (pintype "passive"))
    )
    (net (code "81") (name "Net-(RN1C-1)") (class "Default")
      (node (ref "LED3") (pin "A") (pinfunction "A_A") (pintype "passive"))
      (node (ref "RN1") (pin "4") (pinfunction "1_4") (pintype "passive"))
    )
    (net (code "82") (name "Net-(RN1D-1)") (class "Default")
      (node (ref "LED4") (pin "A") (pinfunction "A_A") (pintype "passive"))
      (node (ref "RN1") (pin "5") (pinfunction "1_5") (pintype "passive"))
    )
    (net (code "83") (name "Net-(RN1E-1)") (class "Default")
      (node (ref "LED5") (pin "A") (pinfunction "A_A") (pintype "passive"))
      (node (ref "RN1") (pin "6") (pinfunction "1_6") (pintype "passive"))
    )
    (net (code "84") (name "Net-(RN1F-1)") (class "Default")
      (node (ref "LED6") (pin "A") (pinfunction "A_A") (pintype "passive"))
      (node (ref "RN1") (pin "7") (pinfunction "1_7") (pintype "passive"))
    )
    (net (code "85") (name "Net-(RN2A-1)") (class "Default")
      (node (ref "LED31") (pin "A") (pinfunction "A_A") (pintype "passive"))
      (node (ref "RN2") (pin "2") (pinfunction "1_2") (pintype "passive"))
    )
    (net (code "86") (name "Net-(RN2B-1)") (class "Default")
      (node (ref "LED32") (pin "A") (pinfunction "A_A") (pintype "passive"))
      (node (ref "RN2") (pin "3") (pinfunction "1_3") (pintype "passive"))
    )
    (net (code "87") (name "Net-(RN2C-1)") (class "Default")
      (node (ref "LED33") (pin "A") (pinfunction "A_A") (pintype "passive"))
      (node (ref "RN2") (pin "4") (pinfunction "1_4") (pintype "passive"))
    )
    (net (code "88") (name "Net-(RN2D-1)") (class "Default")
      (node (ref "LED34") (pin "A") (pinfunction "A_A") (pintype "passive"))
      (node (ref "RN2") (pin "5") (pinfunction "1_5") (pintype "passive"))
    )
    (net (code "89") (name "Net-(RN2E-1)") (class "Default")
      (node (ref "LED35") (pin "A") (pinfunction "A_A") (pintype "passive"))
      (node (ref "RN2") (pin "6") (pinfunction "1_6") (pintype "passive"))
    )
    (net (code "90") (name "Net-(RN2F-1)") (class "Default")
      (node (ref "LED36") (pin "A") (pinfunction "A_A") (pintype "passive"))
      (node (ref "RN2") (pin "7") (pinfunction "1_7") (pintype "passive"))
    )
    (net (code "91") (name "Net-(RN3A-1)") (class "Default")
      (node (ref "LED7") (pin "A") (pinfunction "A_A") (pintype "passive"))
      (node (ref "RN3") (pin "2") (pinfunction "1_2") (pintype "passive"))
    )
    (net (code "92") (name "Net-(RN3B-1)") (class "Default")
      (node (ref "LED8") (pin "A") (pinfunction "A_A") (pintype "passive"))
      (node (ref "RN3") (pin "3") (pinfunction "1_3") (pintype "passive"))
    )
    (net (code "93") (name "Net-(RN3C-1)") (class "Default")
      (node (ref "LED9") (pin "A") (pinfunction "A_A") (pintype "passive"))
      (node (ref "RN3") (pin "4") (pinfunction "1_4") (pintype "passive"))
    )
    (net (code "94") (name "Net-(RN3D-1)") (class "Default")
      (node (ref "LED10") (pin "A") (pinfunction "A_A") (pintype "passive"))
      (node (ref "RN3") (pin "5") (pinfunction "1_5") (pintype "passive"))
    )
    (net (code "95") (name "Net-(RN3E-1)") (class "Default")
      (node (ref "LED11") (pin "A") (pinfunction "A_A") (pintype "passive"))
      (node (ref "RN3") (pin "6") (pinfunction "1_6") (pintype "passive"))
    )
    (net (code "96") (name "Net-(RN3F-1)") (class "Default")
      (node (ref "LED12") (pin "A") (pinfunction "A_A") (pintype "passive"))
      (node (ref "RN3") (pin "7") (pinfunction "1_7") (pintype "passive"))
    )
    (net (code "97") (name "Net-(RN3G-1)") (class "Default")
      (node (ref "LED13") (pin "A") (pinfunction "A_A") (pintype "passive"))
      (node (ref "RN3") (pin "8") (pinfunction "1_8") (pintype "passive"))
    )
    (net (code "98") (name "Net-(RN3H-1)") (class "Default")
      (node (ref "LED14") (pin "A") (pinfunction "A_A") (pintype "passive"))
      (node (ref "RN3") (pin "9") (pinfunction "1_9") (pintype "passive"))
    )
    (net (code "99") (name "Net-(RN4A-1)") (class "Default")
      (node (ref "LED37") (pin "A") (pinfunction "A_A") (pintype "passive"))
      (node (ref "RN4") (pin "2") (pinfunction "1_2") (pintype "passive"))
    )
    (net (code "100") (name "Net-(RN4B-1)") (class "Default")
      (node (ref "LED38") (pin "A") (pinfunction "A_A") (pintype "passive"))
      (node (ref "RN4") (pin "3") (pinfunction "1_3") (pintype "passive"))
    )
    (net (code "101") (name "Net-(RN4C-1)") (class "Default")
      (node (ref "LED39") (pin "A") (pinfunction "A_A") (pintype "passive"))
      (node (ref "RN4") (pin "4") (pinfunction "1_4") (pintype "passive"))
    )
    (net (code "102") (name "Net-(RN4D-1)") (class "Default")
      (node (ref "LED40") (pin "A") (pinfunction "A_A") (pintype "passive"))
      (node (ref "RN4") (pin "5") (pinfunction "1_5") (pintype "passive"))
    )
    (net (code "103") (name "Net-(RN4E-1)") (class "Default")
      (node (ref "LED41") (pin "A") (pinfunction "A_A") (pintype "passive"))
      (node (ref "RN4") (pin "6") (pinfunction "1_6") (pintype "passive"))
    )
    (net (code "104") (name "Net-(RN4F-1)") (class "Default")
      (node (ref "LED42") (pin "A") (pinfunction "A_A") (pintype "passive"))
      (node (ref "RN4") (pin "7") (pinfunction "1_7") (pintype "passive"))
    )
    (net (code "105") (name "Net-(RN4G-1)") (class "Default")
      (node (ref "LED43") (pin "A") (pinfunction "A_A") (pintype "passive"))
      (node (ref "RN4") (pin "8") (pinfunction "1_8") (pintype "passive"))
    )
    (net (code "106") (name "Net-(RN4H-1)") (class "Default")
      (node (ref "LED44") (pin "A") (pinfunction "A_A") (pintype "passive"))
      (node (ref "RN4") (pin "9") (pinfunction "1_9") (pintype "passive"))
    )
    (net (code "107") (name "Net-(RN5A-1)") (class "Default")
      (node (ref "LED15") (pin "A") (pinfunction "A_A") (pintype "passive"))
      (node (ref "RN5") (pin "2") (pinfunction "1_2") (pintype "passive"))
    )
    (net (code "108") (name "Net-(RN5B-1)") (class "Default")
      (node (ref "LED16") (pin "A") (pinfunction "A_A") (pintype "passive"))
      (node (ref "RN5") (pin "3") (pinfunction "1_3") (pintype "passive"))
    )
    (net (code "109") (name "Net-(RN5C-1)") (class "Default")
      (node (ref "LED17") (pin "A") (pinfunction "A_A") (pintype "passive"))
      (node (ref "RN5") (pin "4") (pinfunction "1_4") (pintype "passive"))
    )
    (net (code "110") (name "Net-(RN5D-1)") (class "Default")
      (node (ref "LED18") (pin "A") (pinfunction "A_A") (pintype "passive"))
      (node (ref "RN5") (pin "5") (pinfunction "1_5") (pintype "passive"))
    )
    (net (code "111") (name "Net-(RN5E-1)") (class "Default")
      (node (ref "LED19") (pin "A") (pinfunction "A_A") (pintype "passive"))
      (node (ref "RN5") (pin "6") (pinfunction "1_6") (pintype "passive"))
    )
    (net (code "112") (name "Net-(RN5F-1)") (class "Default")
      (node (ref "LED20") (pin "A") (pinfunction "A_A") (pintype "passive"))
      (node (ref "RN5") (pin "7") (pinfunction "1_7") (pintype "passive"))
    )
    (net (code "113") (name "Net-(RN5G-1)") (class "Default")
      (node (ref "LED21") (pin "A") (pinfunction "A_A") (pintype "passive"))
      (node (ref "RN5") (pin "8") (pinfunction "1_8") (pintype "passive"))
    )
    (net (code "114") (name "Net-(RN5H-1)") (class "Default")
      (node (ref "LED22") (pin "A") (pinfunction "A_A") (pintype "passive"))
      (node (ref "RN5") (pin "9") (pinfunction "1_9") (pintype "passive"))
    )
    (net (code "115") (name "Net-(RN6A-1)") (class "Default")
      (node (ref "LED45") (pin "A") (pinfunction "A_A") (pintype "passive"))
      (node (ref "RN6") (pin "2") (pinfunction "1_2") (pintype "passive"))
    )
    (net (code "116") (name "Net-(RN6B-1)") (class "Default")
      (node (ref "LED46") (pin "A") (pinfunction "A_A") (pintype "passive"))
      (node (ref "RN6") (pin "3") (pinfunction "1_3") (pintype "passive"))
    )
    (net (code "117") (name "Net-(RN6C-1)") (class "Default")
      (node (ref "LED47") (pin "A") (pinfunction "A_A") (pintype "passive"))
      (node (ref "RN6") (pin "4") (pinfunction "1_4") (pintype "passive"))
    )
    (net (code "118") (name "Net-(RN6D-1)") (class "Default")
      (node (ref "LED48") (pin "A") (pinfunction "A_A") (pintype "passive"))
      (node (ref "RN6") (pin "5") (pinfunction "1_5") (pintype "passive"))
    )
    (net (code "119") (name "Net-(RN6E-1)") (class "Default")
      (node (ref "LED49") (pin "A") (pinfunction "A_A") (pintype "passive"))
      (node (ref "RN6") (pin "6") (pinfunction "1_6") (pintype "passive"))
    )
    (net (code "120") (name "Net-(RN6F-1)") (class "Default")
      (node (ref "LED50") (pin "A") (pinfunction "A_A") (pintype "passive"))
      (node (ref "RN6") (pin "7") (pinfunction "1_7") (pintype "passive"))
    )
    (net (code "121") (name "Net-(RN6G-1)") (class "Default")
      (node (ref "LED51") (pin "A") (pinfunction "A_A") (pintype "passive"))
      (node (ref "RN6") (pin "8") (pinfunction "1_8") (pintype "passive"))
    )
    (net (code "122") (name "Net-(RN6H-1)") (class "Default")
      (node (ref "LED52") (pin "A") (pinfunction "A_A") (pintype "passive"))
      (node (ref "RN6") (pin "9") (pinfunction "1_9") (pintype "passive"))
    )
    (net (code "123") (name "Net-(RN7A-1)") (class "Default")
      (node (ref "LED23") (pin "A") (pinfunction "A_A") (pintype "passive"))
      (node (ref "RN7") (pin "2") (pinfunction "1_2") (pintype "passive"))
    )
    (net (code "124") (name "Net-(RN7B-1)") (class "Default")
      (node (ref "LED24") (pin "A") (pinfunction "A_A") (pintype "passive"))
      (node (ref "RN7") (pin "3") (pinfunction "1_3") (pintype "passive"))
    )
    (net (code "125") (name "Net-(RN7C-1)") (class "Default")
      (node (ref "LED25") (pin "A") (pinfunction "A_A") (pintype "passive"))
      (node (ref "RN7") (pin "4") (pinfunction "1_4") (pintype "passive"))
    )
    (net (code "126") (name "Net-(RN7D-1)") (class "Default")
      (node (ref "LED26") (pin "A") (pinfunction "A_A") (pintype "passive"))
      (node (ref "RN7") (pin "5") (pinfunction "1_5") (pintype "passive"))
    )
    (net (code "127") (name "Net-(RN7E-1)") (class "Default")
      (node (ref "LED27") (pin "A") (pinfunction "A_A") (pintype "passive"))
      (node (ref "RN7") (pin "6") (pinfunction "1_6") (pintype "passive"))
    )
    (net (code "128") (name "Net-(RN7F-1)") (class "Default")
      (node (ref "LED28") (pin "A") (pinfunction "A_A") (pintype "passive"))
      (node (ref "RN7") (pin "7") (pinfunction "1_7") (pintype "passive"))
    )
    (net (code "129") (name "Net-(RN7G-1)") (class "Default")
      (node (ref "LED29") (pin "A") (pinfunction "A_A") (pintype "passive"))
      (node (ref "RN7") (pin "8") (pinfunction "1_8") (pintype "passive"))
    )
    (net (code "130") (name "Net-(RN7H-1)") (class "Default")
      (node (ref "LED30") (pin "A") (pinfunction "A_A") (pintype "passive"))
      (node (ref "RN7") (pin "9") (pinfunction "1_9") (pintype "passive"))
    )
    (net (code "131") (name "Net-(RN8A-1)") (class "Default")
      (node (ref "LED53") (pin "A") (pinfunction "A_A") (pintype "passive"))
      (node (ref "RN8") (pin "2") (pinfunction "1_2") (pintype "passive"))
    )
    (net (code "132") (name "Net-(RN8B-1)") (class "Default")
      (node (ref "LED54") (pin "A") (pinfunction "A_A") (pintype "passive"))
      (node (ref "RN8") (pin "3") (pinfunction "1_3") (pintype "passive"))
    )
    (net (code "133") (name "Net-(RN8C-1)") (class "Default")
      (node (ref "LED55") (pin "A") (pinfunction "A_A") (pintype "passive"))
      (node (ref "RN8") (pin "4") (pinfunction "1_4") (pintype "passive"))
    )
    (net (code "134") (name "Net-(RN8D-1)") (class "Default")
      (node (ref "LED56") (pin "A") (pinfunction "A_A") (pintype "passive"))
      (node (ref "RN8") (pin "5") (pinfunction "1_5") (pintype "passive"))
    )
    (net (code "135") (name "Net-(RN8E-1)") (class "Default")
      (node (ref "LED57") (pin "A") (pinfunction "A_A") (pintype "passive"))
      (node (ref "RN8") (pin "6") (pinfunction "1_6") (pintype "passive"))
    )
    (net (code "136") (name "Net-(RN8F-1)") (class "Default")
      (node (ref "LED58") (pin "A") (pinfunction "A_A") (pintype "passive"))
      (node (ref "RN8") (pin "7") (pinfunction "1_7") (pintype "passive"))
    )
    (net (code "137") (name "Net-(RN8G-1)") (class "Default")
      (node (ref "LED59") (pin "A") (pinfunction "A_A") (pintype "passive"))
      (node (ref "RN8") (pin "8") (pinfunction "1_8") (pintype "passive"))
    )
    (net (code "138") (name "Net-(RN8H-1)") (class "Default")
      (node (ref "LED60") (pin "A") (pinfunction "A_A") (pintype "passive"))
      (node (ref "RN8") (pin "9") (pinfunction "1_9") (pintype "passive"))
    )
    (net (code "139") (name "VCC") (class "Default")
      (node (ref "G3") (pin "+") (pinfunction "+_+") (pintype "passive"))
      (node (ref "IC1") (pin "10") (pinfunction "SCL_10") (pintype "input"))
      (node (ref "IC10") (pin "3") (pinfunction "~{WP}_3") (pintype "input"))
      (node (ref "IC10") (pin "7") (pinfunction "~{HOLD}_7") (pintype "input"))
      (node (ref "IC10") (pin "8") (pinfunction "VCC_8") (pintype "power_in"))
      (node (ref "IC2") (pin "10") (pinfunction "SCL_10") (pintype "input"))
      (node (ref "IC3") (pin "10") (pinfunction "SCL_10") (pintype "input"))
      (node (ref "IC4") (pin "10") (pinfunction "SCL_10") (pintype "input"))
      (node (ref "IC5") (pin "10") (pinfunction "SCL_10") (pintype "input"))
      (node (ref "IC6") (pin "10") (pinfunction "SCL_10") (pintype "input"))
      (node (ref "IC7") (pin "10") (pinfunction "SCL_10") (pintype "input"))
      (node (ref "IC8") (pin "10") (pinfunction "SCL_10") (pintype "input"))
      (node (ref "IC9") (pin "20") (pinfunction "VCC_20") (pintype "power_in"))
      (node (ref "R1") (pin "2") (pinfunction "2_2") (pintype "passive"))
      (node (ref "RN1") (pin "1") (pinfunction "1_1") (pintype "passive"))
      (node (ref "RN2") (pin "1") (pinfunction "1_1") (pintype "passive"))
      (node (ref "RN3") (pin "1") (pinfunction "1_1") (pintype "passive"))
      (node (ref "RN4") (pin "1") (pinfunction "1_1") (pintype "passive"))
      (node (ref "RN5") (pin "1") (pinfunction "1_1") (pintype "passive"))
      (node (ref "RN6") (pin "1") (pinfunction "1_1") (pintype "passive"))
      (node (ref "RN7") (pin "1") (pinfunction "1_1") (pintype "passive"))
      (node (ref "RN8") (pin "1") (pinfunction "1_1") (pintype "passive"))
      (node (ref "SV1") (pin "2") (pinfunction "2_2") (pintype "passive"))
      (node (ref "X1") (pin "1") (pinfunction "1_1") (pintype "passive"))
    )
    (net (code "140") (name "unconnected-(G1-+-Pad+@1)") (class "Default")
      (node (ref "G1") (pin "+@1") (pinfunction "+_+@1") (pintype "passive"))
    )
    (net (code "141") (name "unconnected-(G2-+-Pad+@1)") (class "Default")
      (node (ref "G2") (pin "+@1") (pinfunction "+_+@1") (pintype "passive"))
    )
    (net (code "142") (name "unconnected-(G3-+-Pad+@1)") (class "Default")
      (node (ref "G3") (pin "+@1") (pinfunction "+_+@1") (pintype "passive"))
    )
    (net (code "143") (name "unconnected-(IC1A-QA-Pad15)") (class "Default")
      (node (ref "IC1") (pin "15") (pinfunction "QA_15") (pintype "tri_state"))
    )
    (net (code "144") (name "unconnected-(IC1A-QB-Pad1)") (class "Default")
      (node (ref "IC1") (pin "1") (pinfunction "QB_1") (pintype "tri_state"))
    )
    (net (code "145") (name "unconnected-(IC2A-QA-Pad15)") (class "Default")
      (node (ref "IC2") (pin "15") (pinfunction "QA_15") (pintype "tri_state"))
    )
    (net (code "146") (name "unconnected-(IC2A-QB-Pad1)") (class "Default")
      (node (ref "IC2") (pin "1") (pinfunction "QB_1") (pintype "tri_state"))
    )
    (net (code "147") (name "unconnected-(IC7A-QH*-Pad9)") (class "Default")
      (node (ref "IC7") (pin "9") (pinfunction "QH*_9") (pintype "tri_state"))
    )
    (net (code "148") (name "unconnected-(IC8A-QH*-Pad9)") (class "Default")
      (node (ref "IC8") (pin "9") (pinfunction "QH*_9") (pintype "tri_state"))
    )
    (net (code "149") (name "unconnected-(IC9-(AIN0{slash}PCI0)PB0-Pad12)") (class "Default")
      (node (ref "IC9") (pin "12") (pinfunction "(AIN0/PCI0)PB0_12") (pintype "bidirectional"))
    )
    (net (code "150") (name "unconnected-(IC9-(AIN1{slash}PCI1)PB1-Pad13)") (class "Default")
      (node (ref "IC9") (pin "13") (pinfunction "(AIN1/PCI1)PB1_13") (pintype "bidirectional"))
    )
    (net (code "151") (name "unconnected-(IC9-(OC0A{slash}PCI2)PB2-Pad14)") (class "Default")
      (node (ref "IC9") (pin "14") (pinfunction "(OC0A/PCI2)PB2_14") (pintype "bidirectional"))
    )
    (net (code "152") (name "unconnected-(IC9-(OC1A{slash}PCI3)PB3-Pad15)") (class "Default")
      (node (ref "IC9") (pin "15") (pinfunction "(OC1A/PCI3)PB3_15") (pintype "bidirectional"))
    )
    (net (code "153") (name "unconnected-(IC9-(RXD)PD0-Pad2)") (class "Default")
      (node (ref "IC9") (pin "2") (pinfunction "(RXD)PD0_2") (pintype "bidirectional"))
    )
    (net (code "154") (name "unconnected-(IC9-(TXD)PD1-Pad3)") (class "Default")
      (node (ref "IC9") (pin "3") (pinfunction "(TXD)PD1_3") (pintype "bidirectional"))
    )
    (net (code "155") (name "unconnected-(IC9-XTAL1(PA0)-Pad5)") (class "Default")
      (node (ref "IC9") (pin "5") (pinfunction "XTAL1(PA0)_5") (pintype "bidirectional"))
    )
    (net (code "156") (name "unconnected-(IC9-XTAL2(PA1)-Pad4)") (class "Default")
      (node (ref "IC9") (pin "4") (pinfunction "XTAL2(PA1)_4") (pintype "bidirectional"))
    )
    (net (code "157") (name "unconnected-(SV1-Pad3)") (class "Default")
      (node (ref "SV1") (pin "3") (pinfunction "3_3") (pintype "passive"))
    )
  )
)
